# vcf.net
KiCad netlist of a schematic drawn in EAGLE
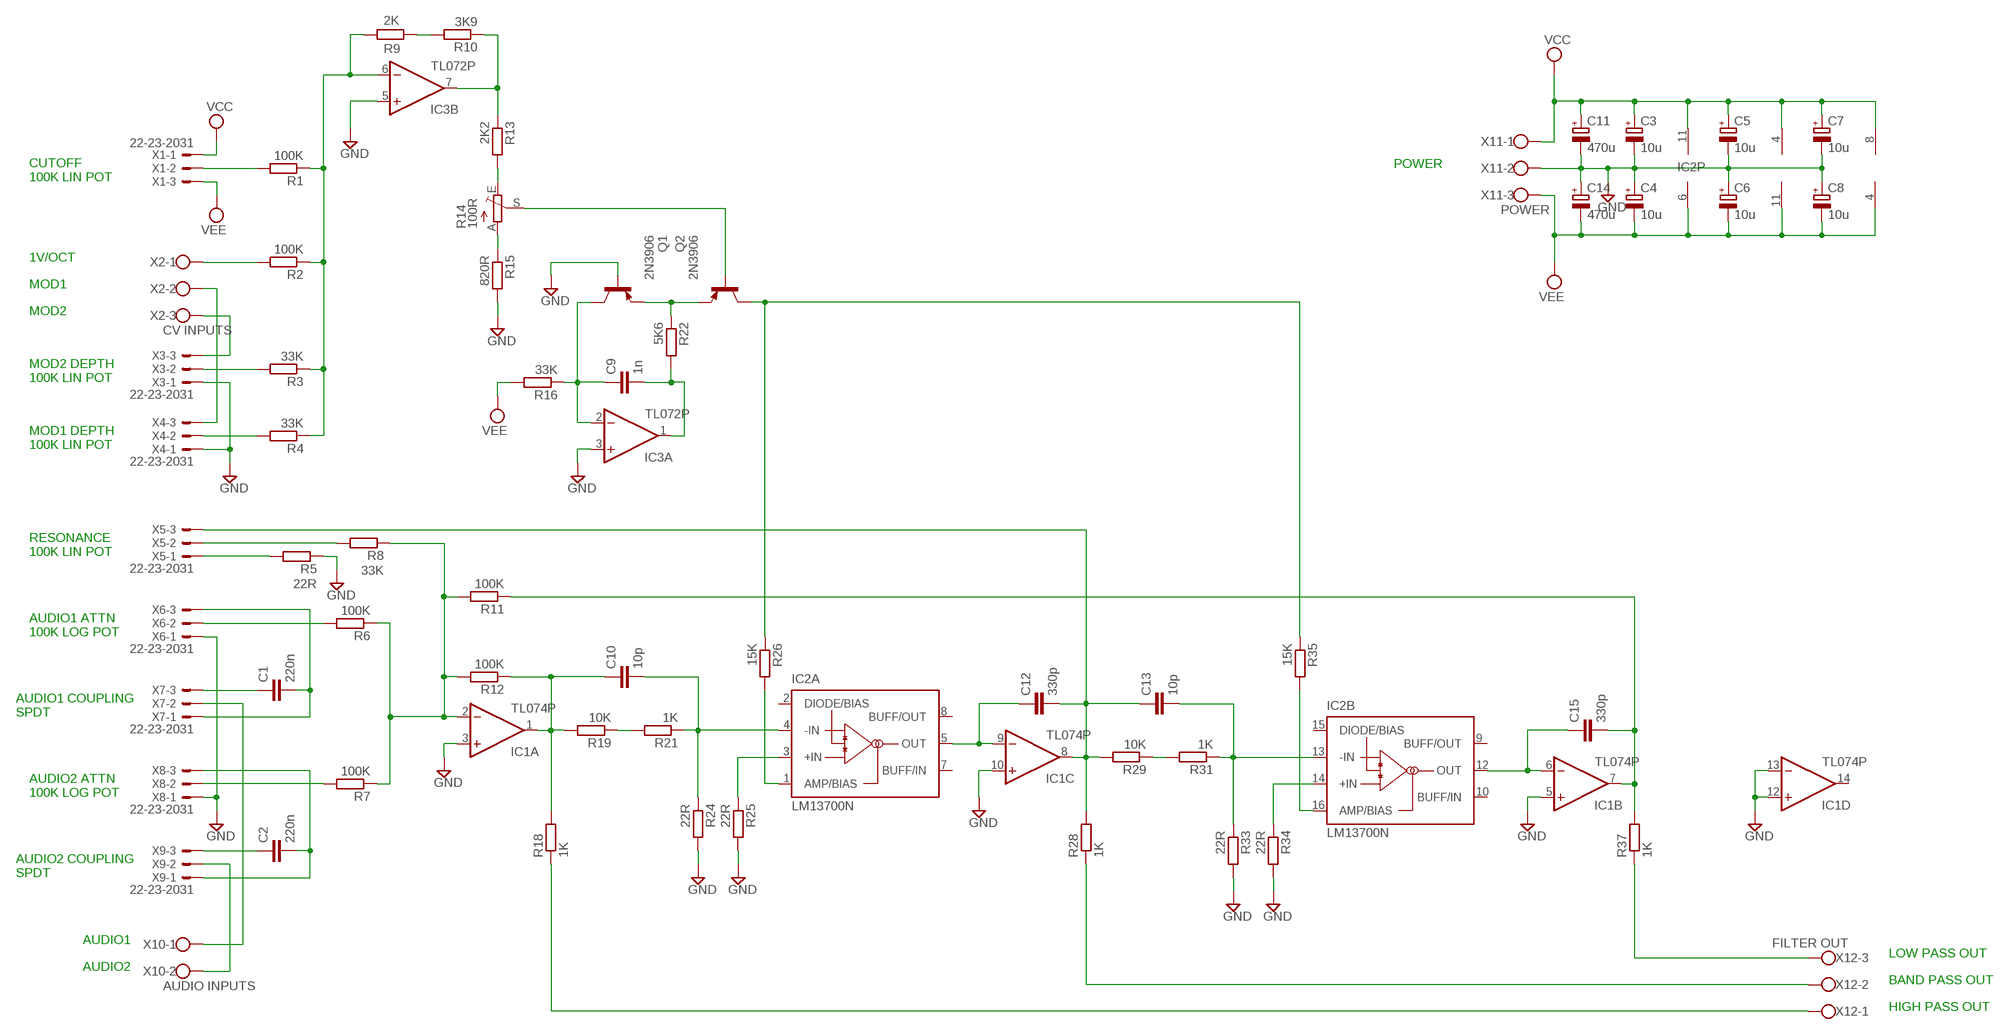
[diagram p0: schematic, sheet 1]

(export (version "E")
  (design (tool "Eeschema 10.0.6"))
  (components
    (comp (ref "C1")
      (value "220n")
      (footprint "eagle-import:C025-025X050")
      (libsource (lib "eagle-import") (part "C-EU025-025X050"))
    )
    (comp (ref "C2")
      (value "220n")
      (footprint "eagle-import:C025-025X050")
      (libsource (lib "eagle-import") (part "C-EU025-025X050"))
    )
    (comp (ref "C3")
      (value "10u")
      (footprint "eagle-import:E1,8-4")
      (libsource (lib "eagle-import") (part "CPOL-EUE1.8-4"))
    )
    (comp (ref "C4")
      (value "10u")
      (footprint "eagle-import:E1,8-4")
      (libsource (lib "eagle-import") (part "CPOL-EUE1.8-4"))
    )
    (comp (ref "C5")
      (value "10u")
      (footprint "eagle-import:E1,8-4")
      (libsource (lib "eagle-import") (part "CPOL-EUE1.8-4"))
    )
    (comp (ref "C6")
      (value "10u")
      (footprint "eagle-import:E1,8-4")
      (libsource (lib "eagle-import") (part "CPOL-EUE1.8-4"))
    )
    (comp (ref "C7")
      (value "10u")
      (footprint "eagle-import:E1,8-4")
      (libsource (lib "eagle-import") (part "CPOL-EUE1.8-4"))
    )
    (comp (ref "C8")
      (value "10u")
      (footprint "eagle-import:E1,8-4")
      (libsource (lib "eagle-import") (part "CPOL-EUE1.8-4"))
    )
    (comp (ref "C9")
      (value "1n")
      (footprint "eagle-import:C025-024X044")
      (libsource (lib "eagle-import") (part "C-EU025-024X044"))
    )
    (comp (ref "C10")
      (value "10p")
      (footprint "eagle-import:C025-024X044")
      (libsource (lib "eagle-import") (part "C-EU025-024X044"))
    )
    (comp (ref "C11")
      (value "470u")
      (footprint "eagle-import:E2,5-6")
      (libsource (lib "eagle-import") (part "CPOL-EUE2.5-6"))
    )
    (comp (ref "C12")
      (value "330p")
      (footprint "eagle-import:C025-024X044")
      (libsource (lib "eagle-import") (part "C-EU025-024X044"))
    )
    (comp (ref "C13")
      (value "10p")
      (footprint "eagle-import:C025-024X044")
      (libsource (lib "eagle-import") (part "C-EU025-024X044"))
    )
    (comp (ref "C14")
      (value "470u")
      (footprint "eagle-import:E2,5-6")
      (libsource (lib "eagle-import") (part "CPOL-EUE2.5-6"))
    )
    (comp (ref "C15")
      (value "330p")
      (footprint "eagle-import:C025-024X044")
      (libsource (lib "eagle-import") (part "C-EU025-024X044"))
    )
    (comp (ref "IC1")
      (value "TL074P")
      (footprint "eagle-import:DIL14")
      (libsource (lib "eagle-import") (part "TL074P"))
    )
    (comp (ref "IC2")
      (value "LM13700N")
      (footprint "eagle-import:DIL16")
      (libsource (lib "eagle-import") (part "LM13600N"))
    )
    (comp (ref "IC3")
      (value "TL072P")
      (footprint "eagle-import:DIL08")
      (libsource (lib "eagle-import") (part "TL072P"))
    )
    (comp (ref "Q1")
      (value "2N3906")
      (footprint "eagle-import:TO92")
      (libsource (lib "eagle-import") (part "2N3906"))
    )
    (comp (ref "Q2")
      (value "2N3906")
      (footprint "eagle-import:TO92")
      (libsource (lib "eagle-import") (part "2N3906"))
    )
    (comp (ref "R1")
      (value "100K")
      (footprint "eagle-import:0204_7")
      (libsource (lib "eagle-import") (part "R-EU_0204/7"))
    )
    (comp (ref "R2")
      (value "100K")
      (footprint "eagle-import:0204_7")
      (libsource (lib "eagle-import") (part "R-EU_0204/7"))
    )
    (comp (ref "R3")
      (value "33K")
      (footprint "eagle-import:0204_7")
      (libsource (lib "eagle-import") (part "R-EU_0204/7"))
    )
    (comp (ref "R4")
      (value "33K")
      (footprint "eagle-import:0204_7")
      (libsource (lib "eagle-import") (part "R-EU_0204/7"))
    )
    (comp (ref "R5")
      (value "22R")
      (footprint "eagle-import:0204_7")
      (libsource (lib "eagle-import") (part "R-EU_0204/7"))
    )
    (comp (ref "R6")
      (value "100K")
      (footprint "eagle-import:0204_7")
      (libsource (lib "eagle-import") (part "R-EU_0204/7"))
    )
    (comp (ref "R7")
      (value "100K")
      (footprint "eagle-import:0204_7")
      (libsource (lib "eagle-import") (part "R-EU_0204/7"))
    )
    (comp (ref "R8")
      (value "33K")
      (footprint "eagle-import:0204_7")
      (libsource (lib "eagle-import") (part "R-EU_0204/7"))
    )
    (comp (ref "R9")
      (value "2K")
      (footprint "eagle-import:0309_12")
      (libsource (lib "eagle-import") (part "R-EU_0309/12"))
    )
    (comp (ref "R10")
      (value "3K9")
      (footprint "eagle-import:0204_7")
      (libsource (lib "eagle-import") (part "R-EU_0204/7"))
    )
    (comp (ref "R11")
      (value "100K")
      (footprint "eagle-import:0204_7")
      (libsource (lib "eagle-import") (part "R-EU_0204/7"))
    )
    (comp (ref "R12")
      (value "100K")
      (footprint "eagle-import:0204_7")
      (libsource (lib "eagle-import") (part "R-EU_0204/7"))
    )
    (comp (ref "R13")
      (value "2K2")
      (footprint "eagle-import:0204_7")
      (libsource (lib "eagle-import") (part "R-EU_0204/7"))
    )
    (comp (ref "R14")
      (value "100R")
      (footprint "eagle-import:CA6V")
      (libsource (lib "eagle-import") (part "TRIM_EU-CA6V"))
    )
    (comp (ref "R15")
      (value "820R")
      (footprint "eagle-import:0204_7")
      (libsource (lib "eagle-import") (part "R-EU_0204/7"))
    )
    (comp (ref "R16")
      (value "33K")
      (footprint "eagle-import:0204_7")
      (libsource (lib "eagle-import") (part "R-EU_0204/7"))
    )
    (comp (ref "R18")
      (value "1K")
      (footprint "eagle-import:0204_7")
      (libsource (lib "eagle-import") (part "R-EU_0204/7"))
    )
    (comp (ref "R19")
      (value "10K")
      (footprint "eagle-import:0204_7")
      (libsource (lib "eagle-import") (part "R-EU_0204/7"))
    )
    (comp (ref "R21")
      (value "1K")
      (footprint "eagle-import:0204_7")
      (libsource (lib "eagle-import") (part "R-EU_0204/7"))
    )
    (comp (ref "R22")
      (value "5K6")
      (footprint "eagle-import:0204_7")
      (libsource (lib "eagle-import") (part "R-EU_0204/7"))
    )
    (comp (ref "R24")
      (value "22R")
      (footprint "eagle-import:0204_7")
      (libsource (lib "eagle-import") (part "R-EU_0204/7"))
    )
    (comp (ref "R25")
      (value "22R")
      (footprint "eagle-import:0204_7")
      (libsource (lib "eagle-import") (part "R-EU_0204/7"))
    )
    (comp (ref "R26")
      (value "15K")
      (footprint "eagle-import:0204_7")
      (libsource (lib "eagle-import") (part "R-EU_0204/7"))
    )
    (comp (ref "R28")
      (value "1K")
      (footprint "eagle-import:0204_7")
      (libsource (lib "eagle-import") (part "R-EU_0204/7"))
    )
    (comp (ref "R29")
      (value "10K")
      (footprint "eagle-import:0204_7")
      (libsource (lib "eagle-import") (part "R-EU_0204/7"))
    )
    (comp (ref "R31")
      (value "1K")
      (footprint "eagle-import:0204_7")
      (libsource (lib "eagle-import") (part "R-EU_0204/7"))
    )
    (comp (ref "R33")
      (value "22R")
      (footprint "eagle-import:0204_7")
      (libsource (lib "eagle-import") (part "R-EU_0204/7"))
    )
    (comp (ref "R34")
      (value "22R")
      (footprint "eagle-import:0204_7")
      (libsource (lib "eagle-import") (part "R-EU_0204/7"))
    )
    (comp (ref "R35")
      (value "15K")
      (footprint "eagle-import:0204_7")
      (libsource (lib "eagle-import") (part "R-EU_0204/7"))
    )
    (comp (ref "R37")
      (value "1K")
      (footprint "eagle-import:0204_7")
      (libsource (lib "eagle-import") (part "R-EU_0204/7"))
    )
    (comp (ref "X1")
      (value "22-23-2031")
      (footprint "eagle-import:22-23-2031")
      (fields (field (name "MF") "MOLEX"))
      (libsource (lib "eagle-import") (part "22-23-2031"))
    )
    (comp (ref "X2")
      (value "CV INPUTS")
      (footprint "eagle-import:W237-103")
      (fields (field (name "MPN") "237-103"))
      (libsource (lib "eagle-import") (part "W237-103"))
    )
    (comp (ref "X3")
      (value "22-23-2031")
      (footprint "eagle-import:22-23-2031")
      (fields (field (name "MF") "MOLEX"))
      (libsource (lib "eagle-import") (part "22-23-2031"))
    )
    (comp (ref "X4")
      (value "22-23-2031")
      (footprint "eagle-import:22-23-2031")
      (fields (field (name "MF") "MOLEX"))
      (libsource (lib "eagle-import") (part "22-23-2031"))
    )
    (comp (ref "X5")
      (value "22-23-2031")
      (footprint "eagle-import:22-23-2031")
      (fields (field (name "MF") "MOLEX"))
      (libsource (lib "eagle-import") (part "22-23-2031"))
    )
    (comp (ref "X6")
      (value "22-23-2031")
      (footprint "eagle-import:22-23-2031")
      (fields (field (name "MF") "MOLEX"))
      (libsource (lib "eagle-import") (part "22-23-2031"))
    )
    (comp (ref "X7")
      (value "22-23-2031")
      (footprint "eagle-import:22-23-2031")
      (fields (field (name "MF") "MOLEX"))
      (libsource (lib "eagle-import") (part "22-23-2031"))
    )
    (comp (ref "X8")
      (value "22-23-2031")
      (footprint "eagle-import:22-23-2031")
      (fields (field (name "MF") "MOLEX"))
      (libsource (lib "eagle-import") (part "22-23-2031"))
    )
    (comp (ref "X9")
      (value "22-23-2031")
      (footprint "eagle-import:22-23-2031")
      (fields (field (name "MF") "MOLEX"))
      (libsource (lib "eagle-import") (part "22-23-2031"))
    )
    (comp (ref "X10")
      (value "AUDIO INPUTS")
      (footprint "eagle-import:W237-102")
      (fields (field (name "MPN") "237-102"))
      (libsource (lib "eagle-import") (part "W237-102"))
    )
    (comp (ref "X11")
      (value "POWER")
      (footprint "eagle-import:W237-103")
      (fields (field (name "MPN") "237-103"))
      (libsource (lib "eagle-import") (part "W237-103"))
    )
    (comp (ref "X12")
      (value "FILTER OUT")
      (footprint "eagle-import:W237-103")
      (fields (field (name "MPN") "237-103"))
      (libsource (lib "eagle-import") (part "W237-103"))
    )
  )
  (nets
    (net (code "1") (name "GND") (class "Default")
      (node (ref "C11") (pin "-") (pinfunction "-_-") (pintype "passive"))
      (node (ref "C14") (pin "+") (pinfunction "+_+") (pintype "passive"))
      (node (ref "C3") (pin "-") (pinfunction "-_-") (pintype "passive"))
      (node (ref "C4") (pin "+") (pinfunction "+_+") (pintype "passive"))
      (node (ref "C5") (pin "-") (pinfunction "-_-") (pintype "passive"))
      (node (ref "C6") (pin "+") (pinfunction "+_+") (pintype "passive"))
      (node (ref "C7") (pin "-") (pinfunction "-_-") (pintype "passive"))
      (node (ref "C8") (pin "+") (pinfunction "+_+") (pintype "passive"))
      (node (ref "IC1") (pin "10") (pinfunction "+IN_10") (pintype "input"))
      (node (ref "IC1") (pin "12") (pinfunction "+IN_12") (pintype "input"))
      (node (ref "IC1") (pin "13") (pinfunction "-IN_13") (pintype "input"))
      (node (ref "IC1") (pin "3") (pinfunction "+IN_3") (pintype "input"))
      (node (ref "IC1") (pin "5") (pinfunction "+IN_5") (pintype "input"))
      (node (ref "IC3") (pin "3") (pinfunction "+IN_3") (pintype "input"))
      (node (ref "IC3") (pin "5") (pinfunction "+IN_5") (pintype "input"))
      (node (ref "Q1") (pin "2") (pinfunction "B_2") (pintype "passive"))
      (node (ref "R15") (pin "2") (pinfunction "2_2") (pintype "passive"))
      (node (ref "R24") (pin "2") (pinfunction "2_2") (pintype "passive"))
      (node (ref "R25") (pin "2") (pinfunction "2_2") (pintype "passive"))
      (node (ref "R33") (pin "2") (pinfunction "2_2") (pintype "passive"))
      (node (ref "R34") (pin "2") (pinfunction "2_2") (pintype "passive"))
      (node (ref "R5") (pin "1") (pinfunction "1_1") (pintype "passive"))
      (node (ref "X11") (pin "2") (pinfunction "KL_2") (pintype "passive"))
      (node (ref "X3") (pin "1") (pinfunction "S_1") (pintype "passive"))
      (node (ref "X4") (pin "1") (pinfunction "S_1") (pintype "passive"))
      (node (ref "X6") (pin "1") (pinfunction "S_1") (pintype "passive"))
      (node (ref "X8") (pin "1") (pinfunction "S_1") (pintype "passive"))
    )
    (net (code "2") (name "Net-(IC1A--IN)") (class "Default")
      (node (ref "IC1") (pin "2") (pinfunction "-IN_2") (pintype "input"))
      (node (ref "R11") (pin "2") (pinfunction "2_2") (pintype "passive"))
      (node (ref "R12") (pin "2") (pinfunction "2_2") (pintype "passive"))
      (node (ref "R6") (pin "1") (pinfunction "1_1") (pintype "passive"))
      (node (ref "R7") (pin "1") (pinfunction "1_1") (pintype "passive"))
      (node (ref "R8") (pin "1") (pinfunction "1_1") (pintype "passive"))
    )
    (net (code "3") (name "Net-(IC1A-OUT)") (class "Default")
      (node (ref "C10") (pin "1") (pinfunction "1_1") (pintype "passive"))
      (node (ref "IC1") (pin "1") (pinfunction "OUT_1") (pintype "output"))
      (node (ref "R12") (pin "1") (pinfunction "1_1") (pintype "passive"))
      (node (ref "R18") (pin "2") (pinfunction "2_2") (pintype "passive"))
      (node (ref "R19") (pin "2") (pinfunction "2_2") (pintype "passive"))
    )
    (net (code "4") (name "Net-(IC1B--IN)") (class "Default")
      (node (ref "C15") (pin "1") (pinfunction "1_1") (pintype "passive"))
      (node (ref "IC1") (pin "6") (pinfunction "-IN_6") (pintype "input"))
      (node (ref "IC2") (pin "12") (pinfunction "OUT_12") (pintype "output"))
    )
    (net (code "5") (name "Net-(IC1B-OUT)") (class "Default")
      (node (ref "C15") (pin "2") (pinfunction "2_2") (pintype "passive"))
      (node (ref "IC1") (pin "7") (pinfunction "OUT_7") (pintype "output"))
      (node (ref "R11") (pin "1") (pinfunction "1_1") (pintype "passive"))
      (node (ref "R37") (pin "2") (pinfunction "2_2") (pintype "passive"))
    )
    (net (code "6") (name "Net-(IC1C--IN)") (class "Default")
      (node (ref "C12") (pin "1") (pinfunction "1_1") (pintype "passive"))
      (node (ref "IC1") (pin "9") (pinfunction "-IN_9") (pintype "input"))
      (node (ref "IC2") (pin "5") (pinfunction "OUT_5") (pintype "output"))
    )
    (net (code "7") (name "Net-(IC1C-OUT)") (class "Default")
      (node (ref "C12") (pin "2") (pinfunction "2_2") (pintype "passive"))
      (node (ref "C13") (pin "1") (pinfunction "1_1") (pintype "passive"))
      (node (ref "IC1") (pin "8") (pinfunction "OUT_8") (pintype "output"))
      (node (ref "R28") (pin "2") (pinfunction "2_2") (pintype "passive"))
      (node (ref "R29") (pin "2") (pinfunction "2_2") (pintype "passive"))
      (node (ref "X5") (pin "3") (pinfunction "S_3") (pintype "passive"))
    )
    (net (code "8") (name "Net-(IC2A-+IN)") (class "Default")
      (node (ref "IC2") (pin "3") (pinfunction "+IN_3") (pintype "input"))
      (node (ref "R25") (pin "1") (pinfunction "1_1") (pintype "passive"))
    )
    (net (code "9") (name "Net-(IC2A--IN)") (class "Default")
      (node (ref "C10") (pin "2") (pinfunction "2_2") (pintype "passive"))
      (node (ref "IC2") (pin "4") (pinfunction "-IN_4") (pintype "input"))
      (node (ref "R21") (pin "1") (pinfunction "1_1") (pintype "passive"))
      (node (ref "R24") (pin "1") (pinfunction "1_1") (pintype "passive"))
    )
    (net (code "10") (name "Net-(IC2A-AMP{slash}BIAS)") (class "Default")
      (node (ref "IC2") (pin "1") (pinfunction "AMP/BIAS_1") (pintype "passive"))
      (node (ref "R26") (pin "2") (pinfunction "2_2") (pintype "passive"))
    )
    (net (code "11") (name "Net-(IC2B-+IN)") (class "Default")
      (node (ref "IC2") (pin "14") (pinfunction "+IN_14") (pintype "input"))
      (node (ref "R34") (pin "1") (pinfunction "1_1") (pintype "passive"))
    )
    (net (code "12") (name "Net-(IC2B--IN)") (class "Default")
      (node (ref "C13") (pin "2") (pinfunction "2_2") (pintype "passive"))
      (node (ref "IC2") (pin "13") (pinfunction "-IN_13") (pintype "input"))
      (node (ref "R31") (pin "1") (pinfunction "1_1") (pintype "passive"))
      (node (ref "R33") (pin "1") (pinfunction "1_1") (pintype "passive"))
    )
    (net (code "13") (name "Net-(IC2B-AMP{slash}BIAS)") (class "Default")
      (node (ref "IC2") (pin "16") (pinfunction "AMP/BIAS_16") (pintype "passive"))
      (node (ref "R35") (pin "2") (pinfunction "2_2") (pintype "passive"))
    )
    (net (code "14") (name "Net-(IC3A--IN)") (class "Default")
      (node (ref "C9") (pin "1") (pinfunction "1_1") (pintype "passive"))
      (node (ref "IC3") (pin "2") (pinfunction "-IN_2") (pintype "input"))
      (node (ref "Q1") (pin "1") (pinfunction "C_1") (pintype "passive"))
      (node (ref "R16") (pin "1") (pinfunction "1_1") (pintype "passive"))
    )
    (net (code "15") (name "Net-(IC3A-OUT)") (class "Default")
      (node (ref "C9") (pin "2") (pinfunction "2_2") (pintype "passive"))
      (node (ref "IC3") (pin "1") (pinfunction "OUT_1") (pintype "output"))
      (node (ref "R22") (pin "2") (pinfunction "2_2") (pintype "passive"))
    )
    (net (code "16") (name "Net-(IC3B--IN)") (class "Default")
      (node (ref "IC3") (pin "6") (pinfunction "-IN_6") (pintype "input"))
      (node (ref "R1") (pin "1") (pinfunction "1_1") (pintype "passive"))
      (node (ref "R2") (pin "1") (pinfunction "1_1") (pintype "passive"))
      (node (ref "R3") (pin "1") (pinfunction "1_1") (pintype "passive"))
      (node (ref "R4") (pin "1") (pinfunction "1_1") (pintype "passive"))
      (node (ref "R9") (pin "1") (pinfunction "1_1") (pintype "passive"))
    )
    (net (code "17") (name "Net-(IC3B-OUT)") (class "Default")
      (node (ref "IC3") (pin "7") (pinfunction "OUT_7") (pintype "output"))
      (node (ref "R10") (pin "1") (pinfunction "1_1") (pintype "passive"))
      (node (ref "R13") (pin "1") (pinfunction "1_1") (pintype "passive"))
    )
    (net (code "18") (name "Net-(Q1-E)") (class "Default")
      (node (ref "Q1") (pin "3") (pinfunction "E_3") (pintype "passive"))
      (node (ref "Q2") (pin "3") (pinfunction "E_3") (pintype "passive"))
      (node (ref "R22") (pin "1") (pinfunction "1_1") (pintype "passive"))
    )
    (net (code "19") (name "Net-(Q2-B)") (class "Default")
      (node (ref "Q2") (pin "2") (pinfunction "B_2") (pintype "passive"))
      (node (ref "R14") (pin "S") (pinfunction "S_S") (pintype "passive"))
    )
    (net (code "20") (name "Net-(Q2-C)") (class "Default")
      (node (ref "Q2") (pin "1") (pinfunction "C_1") (pintype "passive"))
      (node (ref "R26") (pin "1") (pinfunction "1_1") (pintype "passive"))
      (node (ref "R35") (pin "1") (pinfunction "1_1") (pintype "passive"))
    )
    (net (code "21") (name "Net-(R10-Pad2)") (class "Default")
      (node (ref "R10") (pin "2") (pinfunction "2_2") (pintype "passive"))
      (node (ref "R9") (pin "2") (pinfunction "2_2") (pintype "passive"))
    )
    (net (code "22") (name "Net-(R13-Pad2)") (class "Default")
      (node (ref "R13") (pin "2") (pinfunction "2_2") (pintype "passive"))
      (node (ref "R14") (pin "E") (pinfunction "E_E") (pintype "passive"))
    )
    (net (code "23") (name "Net-(R14-PadA)") (class "Default")
      (node (ref "R14") (pin "A") (pinfunction "A_A") (pintype "passive"))
      (node (ref "R15") (pin "1") (pinfunction "1_1") (pintype "passive"))
    )
    (net (code "24") (name "Net-(R19-Pad1)") (class "Default")
      (node (ref "R19") (pin "1") (pinfunction "1_1") (pintype "passive"))
      (node (ref "R21") (pin "2") (pinfunction "2_2") (pintype "passive"))
    )
    (net (code "25") (name "Net-(R29-Pad1)") (class "Default")
      (node (ref "R29") (pin "1") (pinfunction "1_1") (pintype "passive"))
      (node (ref "R31") (pin "2") (pinfunction "2_2") (pintype "passive"))
    )
    (net (code "26") (name "Net-(X1B-S)") (class "Default")
      (node (ref "R1") (pin "2") (pinfunction "2_2") (pintype "passive"))
      (node (ref "X1") (pin "2") (pinfunction "S_2") (pintype "passive"))
    )
    (net (code "27") (name "Net-(X2A-KL)") (class "Default")
      (node (ref "R2") (pin "2") (pinfunction "2_2") (pintype "passive"))
      (node (ref "X2") (pin "1") (pinfunction "KL_1") (pintype "passive"))
    )
    (net (code "28") (name "Net-(X2B-KL)") (class "Default")
      (node (ref "X2") (pin "2") (pinfunction "KL_2") (pintype "passive"))
      (node (ref "X4") (pin "3") (pinfunction "S_3") (pintype "passive"))
    )
    (net (code "29") (name "Net-(X2C-KL)") (class "Default")
      (node (ref "X2") (pin "3") (pinfunction "KL_3") (pintype "passive"))
      (node (ref "X3") (pin "3") (pinfunction "S_3") (pintype "passive"))
    )
    (net (code "30") (name "Net-(X3B-S)") (class "Default")
      (node (ref "R3") (pin "2") (pinfunction "2_2") (pintype "passive"))
      (node (ref "X3") (pin "2") (pinfunction "S_2") (pintype "passive"))
    )
    (net (code "31") (name "Net-(X4B-S)") (class "Default")
      (node (ref "R4") (pin "2") (pinfunction "2_2") (pintype "passive"))
      (node (ref "X4") (pin "2") (pinfunction "S_2") (pintype "passive"))
    )
    (net (code "32") (name "Net-(X5A-S)") (class "Default")
      (node (ref "R5") (pin "2") (pinfunction "2_2") (pintype "passive"))
      (node (ref "X5") (pin "1") (pinfunction "S_1") (pintype "passive"))
    )
    (net (code "33") (name "Net-(X5B-S)") (class "Default")
      (node (ref "R8") (pin "2") (pinfunction "2_2") (pintype "passive"))
      (node (ref "X5") (pin "2") (pinfunction "S_2") (pintype "passive"))
    )
    (net (code "34") (name "Net-(X6B-S)") (class "Default")
      (node (ref "R6") (pin "2") (pinfunction "2_2") (pintype "passive"))
      (node (ref "X6") (pin "2") (pinfunction "S_2") (pintype "passive"))
    )
    (net (code "35") (name "Net-(X6C-S)") (class "Default")
      (node (ref "C1") (pin "2") (pinfunction "2_2") (pintype "passive"))
      (node (ref "X6") (pin "3") (pinfunction "S_3") (pintype "passive"))
      (node (ref "X7") (pin "1") (pinfunction "S_1") (pintype "passive"))
    )
    (net (code "36") (name "Net-(X7C-S)") (class "Default")
      (node (ref "C1") (pin "1") (pinfunction "1_1") (pintype "passive"))
      (node (ref "X7") (pin "3") (pinfunction "S_3") (pintype "passive"))
    )
    (net (code "37") (name "Net-(X8B-S)") (class "Default")
      (node (ref "R7") (pin "2") (pinfunction "2_2") (pintype "passive"))
      (node (ref "X8") (pin "2") (pinfunction "S_2") (pintype "passive"))
    )
    (net (code "38") (name "Net-(X8C-S)") (class "Default")
      (node (ref "C2") (pin "2") (pinfunction "2_2") (pintype "passive"))
      (node (ref "X8") (pin "3") (pinfunction "S_3") (pintype "passive"))
      (node (ref "X9") (pin "1") (pinfunction "S_1") (pintype "passive"))
    )
    (net (code "39") (name "Net-(X9C-S)") (class "Default")
      (node (ref "C2") (pin "1") (pinfunction "1_1") (pintype "passive"))
      (node (ref "X9") (pin "3") (pinfunction "S_3") (pintype "passive"))
    )
    (net (code "40") (name "Net-(X10A-KL)") (class "Default")
      (node (ref "X10") (pin "1") (pinfunction "KL_1") (pintype "passive"))
      (node (ref "X7") (pin "2") (pinfunction "S_2") (pintype "passive"))
    )
    (net (code "41") (name "Net-(X10B-KL)") (class "Default")
      (node (ref "X10") (pin "2") (pinfunction "KL_2") (pintype "passive"))
      (node (ref "X9") (pin "2") (pinfunction "S_2") (pintype "passive"))
    )
    (net (code "42") (name "Net-(X12A-KL)") (class "Default")
      (node (ref "R18") (pin "1") (pinfunction "1_1") (pintype "passive"))
      (node (ref "X12") (pin "1") (pinfunction "KL_1") (pintype "passive"))
    )
    (net (code "43") (name "Net-(X12B-KL)") (class "Default")
      (node (ref "R28") (pin "1") (pinfunction "1_1") (pintype "passive"))
      (node (ref "X12") (pin "2") (pinfunction "KL_2") (pintype "passive"))
    )
    (net (code "44") (name "Net-(X12C-KL)") (class "Default")
      (node (ref "R37") (pin "1") (pinfunction "1_1") (pintype "passive"))
      (node (ref "X12") (pin "3") (pinfunction "KL_3") (pintype "passive"))
    )
    (net (code "45") (name "VCC") (class "Default")
      (node (ref "C11") (pin "+") (pinfunction "+_+") (pintype "passive"))
      (node (ref "C3") (pin "+") (pinfunction "+_+") (pintype "passive"))
      (node (ref "C5") (pin "+") (pinfunction "+_+") (pintype "passive"))
      (node (ref "C7") (pin "+") (pinfunction "+_+") (pintype "passive"))
      (node (ref "IC1") (pin "4") (pinfunction "V+_4") (pintype "power_in"))
      (node (ref "IC2") (pin "11") (pinfunction "V+_11") (pintype "power_in"))
      (node (ref "IC3") (pin "8") (pinfunction "V+_8") (pintype "power_in"))
      (node (ref "X1") (pin "1") (pinfunction "S_1") (pintype "passive"))
      (node (ref "X11") (pin "1") (pinfunction "KL_1") (pintype "passive"))
    )
    (net (code "46") (name "VEE") (class "Default")
      (node (ref "C14") (pin "-") (pinfunction "-_-") (pintype "passive"))
      (node (ref "C4") (pin "-") (pinfunction "-_-") (pintype "passive"))
      (node (ref "C6") (pin "-") (pinfunction "-_-") (pintype "passive"))
      (node (ref "C8") (pin "-") (pinfunction "-_-") (pintype "passive"))
      (node (ref "IC1") (pin "11") (pinfunction "V-_11") (pintype "power_in"))
      (node (ref "IC2") (pin "6") (pinfunction "V-_6") (pintype "power_in"))
      (node (ref "IC3") (pin "4") (pinfunction "V-_4") (pintype "power_in"))
      (node (ref "R16") (pin "2") (pinfunction "2_2") (pintype "passive"))
      (node (ref "X1") (pin "3") (pinfunction "S_3") (pintype "passive"))
      (node (ref "X11") (pin "3") (pinfunction "KL_3") (pintype "passive"))
    )
    (net (code "47") (name "unconnected-(IC1D-OUT-Pad14)") (class "Default")
      (node (ref "IC1") (pin "14") (pinfunction "OUT_14") (pintype "output"))
    )
    (net (code "48") (name "unconnected-(IC2A-BUFF{slash}IN-Pad7)") (class "Default")
      (node (ref "IC2") (pin "7") (pinfunction "BUFF/IN_7") (pintype "input"))
    )
    (net (code "49") (name "unconnected-(IC2A-BUFF{slash}OUT-Pad8)") (class "Default")
      (node (ref "IC2") (pin "8") (pinfunction "BUFF/OUT_8") (pintype "output"))
    )
    (net (code "50") (name "unconnected-(IC2A-DIODE{slash}BIAS-Pad2)") (class "Default")
      (node (ref "IC2") (pin "2") (pinfunction "DIODE/BIAS_2") (pintype "passive"))
    )
    (net (code "51") (name "unconnected-(IC2B-BUFF{slash}IN-Pad10)") (class "Default")
      (node (ref "IC2") (pin "10") (pinfunction "BUFF/IN_10") (pintype "input"))
    )
    (net (code "52") (name "unconnected-(IC2B-BUFF{slash}OUT-Pad9)") (class "Default")
      (node (ref "IC2") (pin "9") (pinfunction "BUFF/OUT_9") (pintype "output"))
    )
    (net (code "53") (name "unconnected-(IC2B-DIODE{slash}BIAS-Pad15)") (class "Default")
      (node (ref "IC2") (pin "15") (pinfunction "DIODE/BIAS_15") (pintype "passive"))
    )
  )
)
